# ESP32.net
KiCad netlist of a schematic drawn in Altium Designer
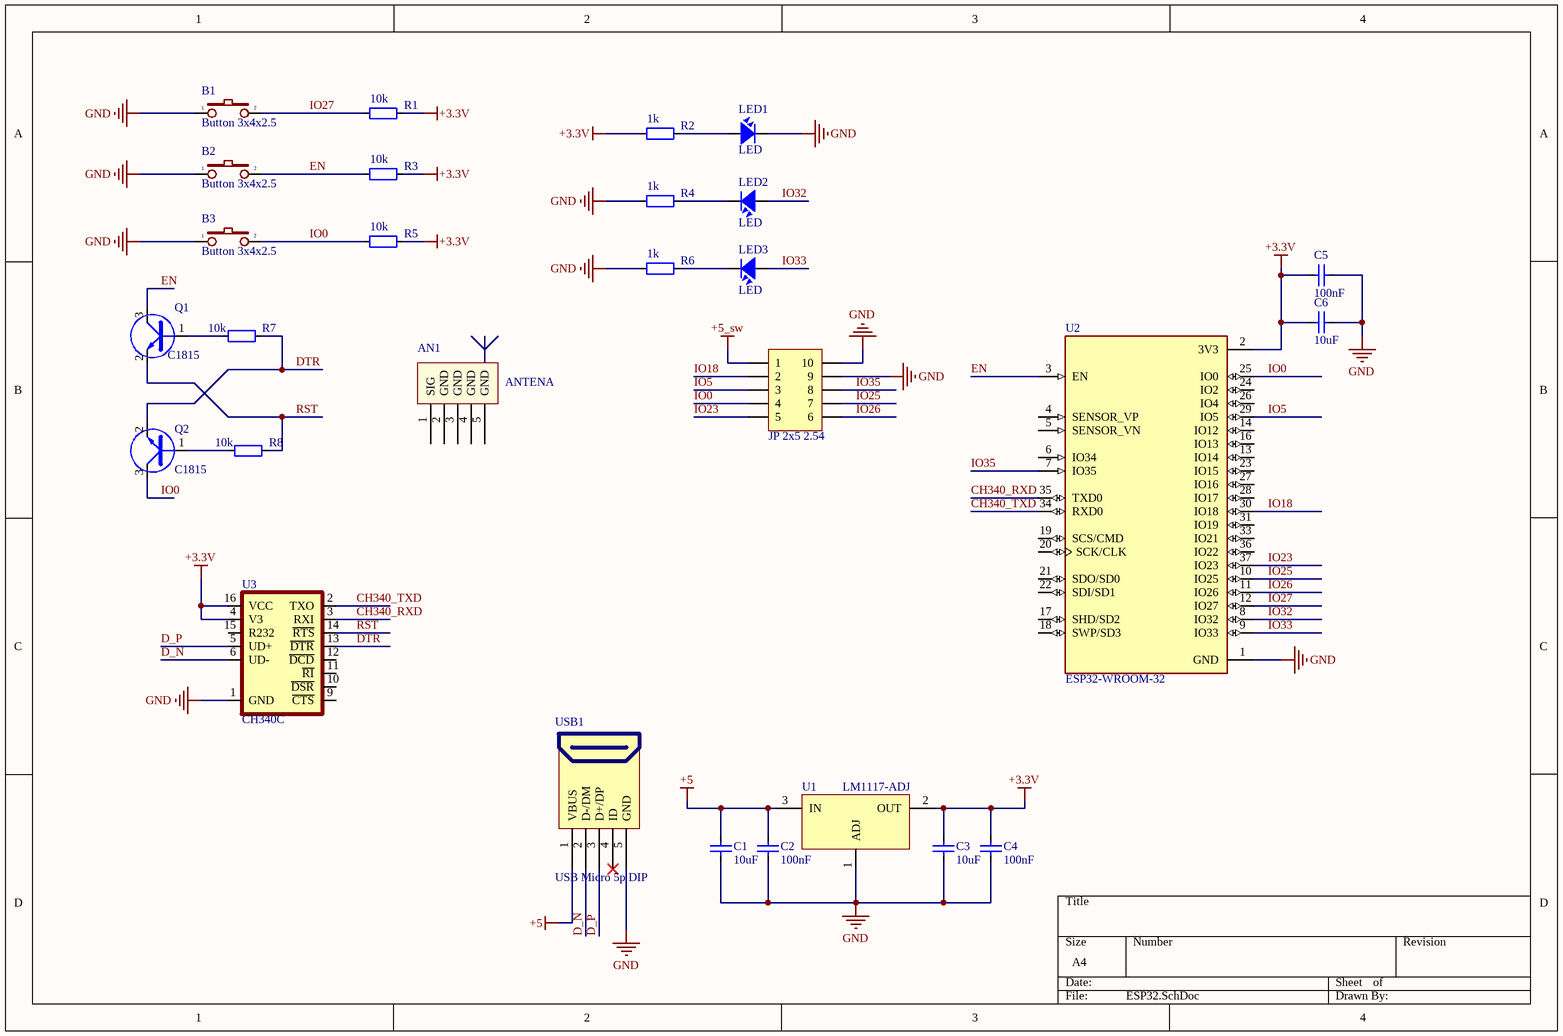
[diagram p0: ESP32.SchDoc]

(export (version "E")
  (design (tool "Eeschema 10.0.6"))
  (components
    (comp (ref "AN1")
      (value "ANTENA")
      (footprint "DE ANTEN SMA CONG")
      (description "Generic Antenna")
      (libsource (lib "Altium_Lib_by_KhueNguyenCreator") (part "ANTEN SMA CONG"))
    )
    (comp (ref "B1")
      (value "Button 3x4x2.5")
      (footprint "Button 3x4x2.5")
      (libsource (lib "My Library") (part "Button 3x4x2.5"))
    )
    (comp (ref "B2")
      (value "Button 3x4x2.5")
      (footprint "Button 3x4x2.5")
      (libsource (lib "My Library") (part "Button 3x4x2.5"))
    )
    (comp (ref "B3")
      (value "Button 3x4x2.5")
      (footprint "Button 3x4x2.5")
      (libsource (lib "My Library") (part "Button 3x4x2.5"))
    )
    (comp (ref "C1")
      (value "10uF")
      (footprint "CAP_0805")
      (description "Capacitor")
      (fields (field (name "PUBLISHER") "Altium Limited"))
      (libsource (lib "My Library") (part "CapSMD"))
    )
    (comp (ref "C2")
      (value "100nF")
      (footprint "CAP_0805")
      (description "Capacitor")
      (fields (field (name "PUBLISHER") "Altium Limited"))
      (libsource (lib "My Library") (part "CapSMD"))
    )
    (comp (ref "C3")
      (value "10uF")
      (footprint "CAP_0805")
      (description "Capacitor")
      (fields (field (name "PUBLISHER") "Altium Limited"))
      (libsource (lib "My Library") (part "CapSMD"))
    )
    (comp (ref "C4")
      (value "100nF")
      (footprint "CAP_0805")
      (description "Capacitor")
      (fields (field (name "PUBLISHER") "Altium Limited"))
      (libsource (lib "My Library") (part "CapSMD"))
    )
    (comp (ref "C5")
      (value "100nF")
      (footprint "CAP_0805")
      (description "Capacitor")
      (fields (field (name "PUBLISHER") "Altium Limited"))
      (libsource (lib "My Library") (part "CapSMD"))
    )
    (comp (ref "C6")
      (value "10uF")
      (footprint "CAP_0805")
      (description "Capacitor")
      (fields (field (name "PUBLISHER") "Altium Limited"))
      (libsource (lib "My Library") (part "CapSMD"))
    )
    (comp (ref "JP1")
      (value "JP 2x5 2.54")
      (footprint "JP 2x5 DT")
      (description "Cắm")
      (libsource (lib "Altium_Lib_by_KhueNguyenCreator") (part "JP 2x5 2.54 Duc Thang"))
    )
    (comp (ref "LED1")
      (value "LED")
      (footprint "LED-0805-Red")
      (description "LED Single colour Green and Red")
      (libsource (lib "My Library") (part "LED"))
    )
    (comp (ref "LED2")
      (value "LED")
      (footprint "LED-0805-Red")
      (description "LED Single colour Green and Red")
      (libsource (lib "My Library") (part "LED"))
    )
    (comp (ref "LED3")
      (value "LED")
      (footprint "LED-0805-Red")
      (description "LED Single colour Green and Red")
      (libsource (lib "My Library") (part "LED"))
    )
    (comp (ref "Q1")
      (value "C1815")
      (footprint "SOT23D")
      (description "NPN 600mW, ECB")
      (libsource (lib "") (part "2SC1815_1"))
    )
    (comp (ref "Q2")
      (value "C1815")
      (footprint "SOT23D")
      (description "NPN 600mW, ECB")
      (libsource (lib "My Library") (part "2SC1815"))
    )
    (comp (ref "R1")
      (value "10k")
      (footprint "RES-SMD-0805")
      (description "Resistor")
      (fields
        (field (name "MANUFACTURER") "Generic Components")
        (field (name "PUBLISHER") "Altium Hobart Technology Centre")
      )
      (libsource (lib "My Library") (part "Resistor - SMD"))
    )
    (comp (ref "R2")
      (value "1k")
      (footprint "RES-SMD-0805")
      (description "Resistor")
      (fields
        (field (name "MANUFACTURER") "Generic Components")
        (field (name "PUBLISHER") "Altium Hobart Technology Centre")
      )
      (libsource (lib "My Library") (part "Resistor - SMD"))
    )
    (comp (ref "R3")
      (value "10k")
      (footprint "RES-SMD-0805")
      (description "Resistor")
      (fields
        (field (name "MANUFACTURER") "Generic Components")
        (field (name "PUBLISHER") "Altium Hobart Technology Centre")
      )
      (libsource (lib "My Library") (part "Resistor - SMD"))
    )
    (comp (ref "R4")
      (value "1k")
      (footprint "RES-SMD-0805")
      (description "Resistor")
      (fields
        (field (name "MANUFACTURER") "Generic Components")
        (field (name "PUBLISHER") "Altium Hobart Technology Centre")
      )
      (libsource (lib "My Library") (part "Resistor - SMD"))
    )
    (comp (ref "R5")
      (value "10k")
      (footprint "RES-SMD-0805")
      (description "Resistor")
      (fields
        (field (name "MANUFACTURER") "Generic Components")
        (field (name "PUBLISHER") "Altium Hobart Technology Centre")
      )
      (libsource (lib "My Library") (part "Resistor - SMD"))
    )
    (comp (ref "R6")
      (value "1k")
      (footprint "RES-SMD-0805")
      (description "Resistor")
      (fields
        (field (name "MANUFACTURER") "Generic Components")
        (field (name "PUBLISHER") "Altium Hobart Technology Centre")
      )
      (libsource (lib "My Library") (part "Resistor - SMD"))
    )
    (comp (ref "R7")
      (value "10k")
      (footprint "RES-SMD-0805")
      (description "Resistor")
      (fields
        (field (name "MANUFACTURER") "Generic Components")
        (field (name "PUBLISHER") "Altium Hobart Technology Centre")
      )
      (libsource (lib "My Library") (part "Resistor - SMD"))
    )
    (comp (ref "R8")
      (value "10k")
      (footprint "RES-SMD-0805")
      (description "Resistor")
      (fields
        (field (name "MANUFACTURER") "Generic Components")
        (field (name "PUBLISHER") "Altium Hobart Technology Centre")
      )
      (libsource (lib "My Library") (part "Resistor - SMD"))
    )
    (comp (ref "U1")
      (value "LM1117-ADJ")
      (footprint "LM1117-SOP")
      (description "800mA Low-Dropout Linear Regulator")
      (fields (field (name "CREATOR") "Nguyen Ba Bien"))
      (libsource (lib "My Library") (part "LM1117-ADJ"))
    )
    (comp (ref "U2")
      (value "ESP32-WROOM-32")
      (footprint "MODULE_ESP32-WROOM-32")
      (description "Bluetooth, WiFi Transceiver Module 2.4GHz ~ 2.5GHz Surface Mount")
      (fields (field (name "MF") "Espressif Systems") (field (name "DIGI-KEY_PART_NUMBER") "1904-1010-1-ND"))
      (libsource (lib "My Library") (part "ESP32-WROOM-32"))
    )
    (comp (ref "U3")
      (value "CH340C")
      (footprint "SO016")
      (description "USB to serial chip CH340")
      (fields (field (name "MF") "WCH"))
      (libsource (lib "My Library") (part "CH340C"))
    )
    (comp (ref "USB1")
      (value "USB Micro 5p DIP")
      (footprint "USB Micro 5p DIP")
      (description "USB Type B")
      (libsource (lib "Altium_Lib_by_KhueNguyenCreator") (part "USB Micro 5p DIP"))
    )
  )
  (nets
    (net (code "1") (name "+3.3V") (class "Default")
      (node (ref "C3") (pin "1") (pinfunction "1_1") (pintype "passive"))
      (node (ref "C4") (pin "1") (pinfunction "1_1") (pintype "passive"))
      (node (ref "C5") (pin "1") (pinfunction "1_1") (pintype "passive"))
      (node (ref "C6") (pin "1") (pinfunction "1_1") (pintype "passive"))
      (node (ref "R1") (pin "1") (pinfunction "1_1") (pintype "passive"))
      (node (ref "R2") (pin "2") (pinfunction "2_2") (pintype "passive"))
      (node (ref "R3") (pin "1") (pinfunction "1_1") (pintype "passive"))
      (node (ref "R5") (pin "1") (pinfunction "1_1") (pintype "passive"))
      (node (ref "U1") (pin "2") (pinfunction "OUT_2") (pintype "passive"))
      (node (ref "U2") (pin "2") (pinfunction "3V3_2") (pintype "power_in"))
      (node (ref "U3") (pin "16") (pinfunction "VCC_16") (pintype "bidirectional"))
      (node (ref "U3") (pin "4") (pinfunction "V3_4") (pintype "bidirectional"))
    )
    (net (code "2") (name "+5") (class "Default")
      (node (ref "C1") (pin "1") (pinfunction "1_1") (pintype "passive"))
      (node (ref "C2") (pin "1") (pinfunction "1_1") (pintype "passive"))
      (node (ref "U1") (pin "3") (pinfunction "IN_3") (pintype "passive"))
      (node (ref "USB1") (pin "1") (pinfunction "VBUS_1") (pintype "passive"))
    )
    (net (code "3") (name "+5_sw") (class "Default")
      (node (ref "JP1") (pin "1") (pinfunction "1_1") (pintype "passive"))
    )
    (net (code "4") (name "/CH340_RXD") (class "Default")
      (node (ref "U2") (pin "35") (pinfunction "TXD0_35") (pintype "bidirectional"))
      (node (ref "U3") (pin "3") (pinfunction "RXI_3") (pintype "bidirectional"))
    )
    (net (code "5") (name "/CH340_TXD") (class "Default")
      (node (ref "U2") (pin "34") (pinfunction "RXD0_34") (pintype "bidirectional"))
      (node (ref "U3") (pin "2") (pinfunction "TXO_2") (pintype "bidirectional"))
    )
    (net (code "6") (name "/DTR") (class "Default")
      (node (ref "Q2") (pin "2") (pinfunction "E_2") (pintype "passive"))
      (node (ref "R7") (pin "1") (pinfunction "1_1") (pintype "passive"))
      (node (ref "U3") (pin "13") (pinfunction "~{DTR}_13") (pintype "bidirectional"))
    )
    (net (code "7") (name "/D_N") (class "Default")
      (node (ref "U3") (pin "6") (pinfunction "UD-_6") (pintype "bidirectional"))
      (node (ref "USB1") (pin "2") (pinfunction "D-/DM_2") (pintype "passive"))
    )
    (net (code "8") (name "/D_P") (class "Default")
      (node (ref "U3") (pin "5") (pinfunction "UD+_5") (pintype "bidirectional"))
      (node (ref "USB1") (pin "3") (pinfunction "D+/DP_3") (pintype "passive"))
    )
    (net (code "9") (name "/EN") (class "Default")
      (node (ref "B2") (pin "2") (pinfunction "2_2") (pintype "passive"))
      (node (ref "Q1") (pin "3") (pinfunction "C_3") (pintype "passive"))
      (node (ref "R3") (pin "2") (pinfunction "2_2") (pintype "passive"))
      (node (ref "U2") (pin "3") (pinfunction "EN_3") (pintype "input"))
    )
    (net (code "10") (name "/IO0") (class "Default")
      (node (ref "B3") (pin "2") (pinfunction "2_2") (pintype "passive"))
      (node (ref "JP1") (pin "4") (pinfunction "4_4") (pintype "passive"))
      (node (ref "Q2") (pin "3") (pinfunction "C_3") (pintype "passive"))
      (node (ref "R5") (pin "2") (pinfunction "2_2") (pintype "passive"))
      (node (ref "U2") (pin "25") (pinfunction "IO0_25") (pintype "bidirectional"))
    )
    (net (code "11") (name "/IO5") (class "Default")
      (node (ref "JP1") (pin "3") (pinfunction "3_3") (pintype "passive"))
      (node (ref "U2") (pin "29") (pinfunction "IO5_29") (pintype "bidirectional"))
    )
    (net (code "12") (name "/IO18") (class "Default")
      (node (ref "JP1") (pin "2") (pinfunction "2_2") (pintype "passive"))
      (node (ref "U2") (pin "30") (pinfunction "IO18_30") (pintype "bidirectional"))
    )
    (net (code "13") (name "/IO23") (class "Default")
      (node (ref "JP1") (pin "5") (pinfunction "5_5") (pintype "passive"))
      (node (ref "U2") (pin "37") (pinfunction "IO23_37") (pintype "bidirectional"))
    )
    (net (code "14") (name "/IO25") (class "Default")
      (node (ref "JP1") (pin "7") (pinfunction "7_7") (pintype "passive"))
      (node (ref "U2") (pin "10") (pinfunction "IO25_10") (pintype "bidirectional"))
    )
    (net (code "15") (name "/IO26") (class "Default")
      (node (ref "JP1") (pin "6") (pinfunction "6_6") (pintype "passive"))
      (node (ref "U2") (pin "11") (pinfunction "IO26_11") (pintype "bidirectional"))
    )
    (net (code "16") (name "/IO27") (class "Default")
      (node (ref "B1") (pin "2") (pinfunction "2_2") (pintype "passive"))
      (node (ref "R1") (pin "2") (pinfunction "2_2") (pintype "passive"))
      (node (ref "U2") (pin "12") (pinfunction "IO27_12") (pintype "bidirectional"))
    )
    (net (code "17") (name "/IO32") (class "Default")
      (node (ref "LED2") (pin "1") (pinfunction "1_1") (pintype "passive"))
      (node (ref "U2") (pin "8") (pinfunction "IO32_8") (pintype "bidirectional"))
    )
    (net (code "18") (name "/IO33") (class "Default")
      (node (ref "LED3") (pin "1") (pinfunction "1_1") (pintype "passive"))
      (node (ref "U2") (pin "9") (pinfunction "IO33_9") (pintype "bidirectional"))
    )
    (net (code "19") (name "/IO35") (class "Default")
      (node (ref "JP1") (pin "8") (pinfunction "8_8") (pintype "passive"))
      (node (ref "U2") (pin "7") (pinfunction "IO35_7") (pintype "input"))
    )
    (net (code "20") (name "/RST") (class "Default")
      (node (ref "Q1") (pin "2") (pinfunction "E_2") (pintype "passive"))
      (node (ref "R8") (pin "1") (pinfunction "1_1") (pintype "passive"))
      (node (ref "U3") (pin "14") (pinfunction "~{RTS}_14") (pintype "bidirectional"))
    )
    (net (code "21") (name "GND") (class "Default")
      (node (ref "B1") (pin "1") (pinfunction "1_1") (pintype "passive"))
      (node (ref "B2") (pin "1") (pinfunction "1_1") (pintype "passive"))
      (node (ref "B3") (pin "1") (pinfunction "1_1") (pintype "passive"))
      (node (ref "C1") (pin "2") (pinfunction "2_2") (pintype "passive"))
      (node (ref "C2") (pin "2") (pinfunction "2_2") (pintype "passive"))
      (node (ref "C3") (pin "2") (pinfunction "2_2") (pintype "passive"))
      (node (ref "C4") (pin "2") (pinfunction "2_2") (pintype "passive"))
      (node (ref "C5") (pin "2") (pinfunction "2_2") (pintype "passive"))
      (node (ref "C6") (pin "2") (pinfunction "2_2") (pintype "passive"))
      (node (ref "JP1") (pin "10") (pinfunction "10_10") (pintype "passive"))
      (node (ref "JP1") (pin "9") (pinfunction "9_9") (pintype "passive"))
      (node (ref "LED1") (pin "2") (pinfunction "2_2") (pintype "passive"))
      (node (ref "R4") (pin "2") (pinfunction "2_2") (pintype "passive"))
      (node (ref "R6") (pin "2") (pinfunction "2_2") (pintype "passive"))
      (node (ref "U1") (pin "1") (pinfunction "ADJ_1") (pintype "passive"))
      (node (ref "U2") (pin "1") (pinfunction "GND_1") (pintype "power_in"))
      (node (ref "U3") (pin "1") (pinfunction "GND_1") (pintype "bidirectional"))
      (node (ref "USB1") (pin "5") (pinfunction "GND_5") (pintype "passive"))
    )
    (net (code "22") (name "Net-(LED1-Pad1)") (class "Default")
      (node (ref "LED1") (pin "1") (pinfunction "1_1") (pintype "passive"))
      (node (ref "R2") (pin "1") (pinfunction "1_1") (pintype "passive"))
    )
    (net (code "23") (name "Net-(LED2-Pad2)") (class "Default")
      (node (ref "LED2") (pin "2") (pinfunction "2_2") (pintype "passive"))
      (node (ref "R4") (pin "1") (pinfunction "1_1") (pintype "passive"))
    )
    (net (code "24") (name "Net-(LED3-Pad2)") (class "Default")
      (node (ref "LED3") (pin "2") (pinfunction "2_2") (pintype "passive"))
      (node (ref "R6") (pin "1") (pinfunction "1_1") (pintype "passive"))
    )
    (net (code "25") (name "Net-(Q1-B)") (class "Default")
      (node (ref "Q1") (pin "1") (pinfunction "B_1") (pintype "passive"))
      (node (ref "R7") (pin "2") (pinfunction "2_2") (pintype "passive"))
    )
    (net (code "26") (name "Net-(Q2-B)") (class "Default")
      (node (ref "Q2") (pin "1") (pinfunction "B_1") (pintype "passive"))
      (node (ref "R8") (pin "2") (pinfunction "2_2") (pintype "passive"))
    )
    (net (code "27") (name "unconnected-(AN1-GND-Pad2)") (class "Default")
      (node (ref "AN1") (pin "2") (pinfunction "GND_2") (pintype "passive"))
    )
    (net (code "28") (name "unconnected-(AN1-GND-Pad3)") (class "Default")
      (node (ref "AN1") (pin "3") (pinfunction "GND_3") (pintype "passive"))
    )
    (net (code "29") (name "unconnected-(AN1-GND-Pad4)") (class "Default")
      (node (ref "AN1") (pin "4") (pinfunction "GND_4") (pintype "passive"))
    )
    (net (code "30") (name "unconnected-(AN1-GND-Pad5)") (class "Default")
      (node (ref "AN1") (pin "5") (pinfunction "GND_5") (pintype "passive"))
    )
    (net (code "31") (name "unconnected-(AN1-SIG-Pad1)") (class "Default")
      (node (ref "AN1") (pin "1") (pinfunction "SIG_1") (pintype "passive"))
    )
    (net (code "32") (name "unconnected-(U2-IO2-Pad24)") (class "Default")
      (node (ref "U2") (pin "24") (pinfunction "IO2_24") (pintype "bidirectional"))
    )
    (net (code "33") (name "unconnected-(U2-IO4-Pad26)") (class "Default")
      (node (ref "U2") (pin "26") (pinfunction "IO4_26") (pintype "bidirectional"))
    )
    (net (code "34") (name "unconnected-(U2-IO12-Pad14)") (class "Default")
      (node (ref "U2") (pin "14") (pinfunction "IO12_14") (pintype "bidirectional"))
    )
    (net (code "35") (name "unconnected-(U2-IO13-Pad16)") (class "Default")
      (node (ref "U2") (pin "16") (pinfunction "IO13_16") (pintype "bidirectional"))
    )
    (net (code "36") (name "unconnected-(U2-IO14-Pad13)") (class "Default")
      (node (ref "U2") (pin "13") (pinfunction "IO14_13") (pintype "bidirectional"))
    )
    (net (code "37") (name "unconnected-(U2-IO15-Pad23)") (class "Default")
      (node (ref "U2") (pin "23") (pinfunction "IO15_23") (pintype "bidirectional"))
    )
    (net (code "38") (name "unconnected-(U2-IO16-Pad27)") (class "Default")
      (node (ref "U2") (pin "27") (pinfunction "IO16_27") (pintype "bidirectional"))
    )
    (net (code "39") (name "unconnected-(U2-IO17-Pad28)") (class "Default")
      (node (ref "U2") (pin "28") (pinfunction "IO17_28") (pintype "bidirectional"))
    )
    (net (code "40") (name "unconnected-(U2-IO19-Pad31)") (class "Default")
      (node (ref "U2") (pin "31") (pinfunction "IO19_31") (pintype "bidirectional"))
    )
    (net (code "41") (name "unconnected-(U2-IO21-Pad33)") (class "Default")
      (node (ref "U2") (pin "33") (pinfunction "IO21_33") (pintype "bidirectional"))
    )
    (net (code "42") (name "unconnected-(U2-IO22-Pad36)") (class "Default")
      (node (ref "U2") (pin "36") (pinfunction "IO22_36") (pintype "bidirectional"))
    )
    (net (code "43") (name "unconnected-(U2-IO34-Pad6)") (class "Default")
      (node (ref "U2") (pin "6") (pinfunction "IO34_6") (pintype "input"))
    )
    (net (code "44") (name "unconnected-(U2-SCK{slash}CLK-Pad20)") (class "Default")
      (node (ref "U2") (pin "20") (pinfunction "SCK/CLK_20") (pintype "bidirectional"))
    )
    (net (code "45") (name "unconnected-(U2-SCS{slash}CMD-Pad19)") (class "Default")
      (node (ref "U2") (pin "19") (pinfunction "SCS/CMD_19") (pintype "bidirectional"))
    )
    (net (code "46") (name "unconnected-(U2-SDI{slash}SD1-Pad22)") (class "Default")
      (node (ref "U2") (pin "22") (pinfunction "SDI/SD1_22") (pintype "bidirectional"))
    )
    (net (code "47") (name "unconnected-(U2-SDO{slash}SD0-Pad21)") (class "Default")
      (node (ref "U2") (pin "21") (pinfunction "SDO/SD0_21") (pintype "bidirectional"))
    )
    (net (code "48") (name "unconnected-(U2-SENSOR_VN-Pad5)") (class "Default")
      (node (ref "U2") (pin "5") (pinfunction "SENSOR_VN_5") (pintype "input"))
    )
    (net (code "49") (name "unconnected-(U2-SENSOR_VP-Pad4)") (class "Default")
      (node (ref "U2") (pin "4") (pinfunction "SENSOR_VP_4") (pintype "input"))
    )
    (net (code "50") (name "unconnected-(U2-SHD{slash}SD2-Pad17)") (class "Default")
      (node (ref "U2") (pin "17") (pinfunction "SHD/SD2_17") (pintype "bidirectional"))
    )
    (net (code "51") (name "unconnected-(U2-SWP{slash}SD3-Pad18)") (class "Default")
      (node (ref "U2") (pin "18") (pinfunction "SWP/SD3_18") (pintype "bidirectional"))
    )
    (net (code "52") (name "unconnected-(U3-R232-Pad15)") (class "Default")
      (node (ref "U3") (pin "15") (pinfunction "R232_15") (pintype "bidirectional"))
    )
    (net (code "53") (name "unconnected-(U3-~{CTS}-Pad9)") (class "Default")
      (node (ref "U3") (pin "9") (pinfunction "~{CTS}_9") (pintype "bidirectional"))
    )
    (net (code "54") (name "unconnected-(U3-~{DCD}-Pad12)") (class "Default")
      (node (ref "U3") (pin "12") (pinfunction "~{DCD}_12") (pintype "bidirectional"))
    )
    (net (code "55") (name "unconnected-(U3-~{DSR}-Pad10)") (class "Default")
      (node (ref "U3") (pin "10") (pinfunction "~{DSR}_10") (pintype "bidirectional"))
    )
    (net (code "56") (name "unconnected-(U3-~{RI}-Pad11)") (class "Default")
      (node (ref "U3") (pin "11") (pinfunction "~{RI}_11") (pintype "bidirectional"))
    )
    (net (code "57") (name "unconnected-(USB1-ID-Pad4)") (class "Default")
      (node (ref "USB1") (pin "4") (pinfunction "ID_4") (pintype "passive+no_connect"))
    )
  )
)
